# New_Grads_2019_Keychain.net
KiCad netlist of a schematic drawn in EAGLE
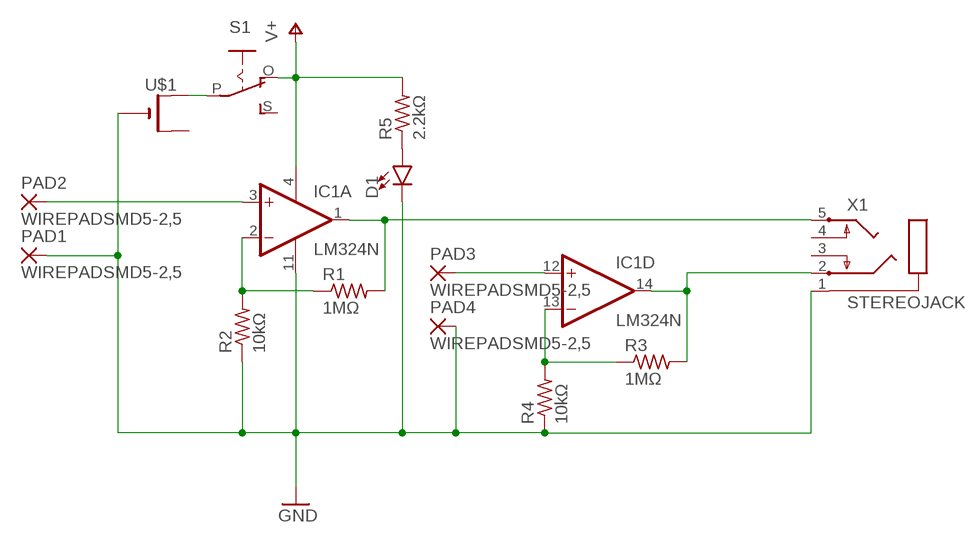
[diagram p0: schematic, sheet 1]

(export (version "E")
  (design (tool "Eeschema 10.0.6"))
  (components
    (comp (ref "D1")
      (value "LED-3MM-NO_SILK")
      (footprint "eagle-import:LED_3MM-NS")
      (libsource (lib "eagle-import") (part "LED-3MM-NO_SILK"))
    )
    (comp (ref "IC1")
      (value "LM324N")
      (footprint "eagle-import:DIL14")
      (libsource (lib "eagle-import") (part "LM324N"))
    )
    (comp (ref "PAD1")
      (value "WIREPADSMD5-2,5")
      (footprint "eagle-import:5-2,5")
      (libsource (lib "eagle-import") (part "WIREPADSMD5-2,5"))
    )
    (comp (ref "PAD2")
      (value "WIREPADSMD5-2,5")
      (footprint "eagle-import:5-2,5")
      (libsource (lib "eagle-import") (part "WIREPADSMD5-2,5"))
    )
    (comp (ref "PAD3")
      (value "WIREPADSMD5-2,5")
      (footprint "eagle-import:5-2,5")
      (libsource (lib "eagle-import") (part "WIREPADSMD5-2,5"))
    )
    (comp (ref "PAD4")
      (value "WIREPADSMD5-2,5")
      (footprint "eagle-import:5-2,5")
      (libsource (lib "eagle-import") (part "WIREPADSMD5-2,5"))
    )
    (comp (ref "R1")
      (value "1MΩ")
      (footprint "eagle-import:0204_5")
      (libsource (lib "eagle-import") (part "R-US_0204/5"))
    )
    (comp (ref "R2")
      (value "10kΩ")
      (footprint "eagle-import:0204_5")
      (libsource (lib "eagle-import") (part "R-US_0204/5"))
    )
    (comp (ref "R3")
      (value "1MΩ")
      (footprint "eagle-import:0204_5")
      (libsource (lib "eagle-import") (part "R-US_0204/5"))
    )
    (comp (ref "R4")
      (value "10kΩ")
      (footprint "eagle-import:0204_5")
      (libsource (lib "eagle-import") (part "R-US_0204/5"))
    )
    (comp (ref "R5")
      (value "2.2kΩ")
      (footprint "eagle-import:0204_5")
      (libsource (lib "eagle-import") (part "R-US_0204/5"))
    )
    (comp (ref "S1")
      (value "EG1218S")
      (footprint "eagle-import:EG1218")
      (libsource (lib "eagle-import") (part "EG1218S"))
    )
    (comp (ref "U$1")
      (value "CR1220THM")
      (footprint "eagle-import:CR1220-THM")
      (libsource (lib "eagle-import") (part "CR1220THM"))
    )
    (comp (ref "X1")
      (value "STEREOJACK")
      (footprint "eagle-import:STX3100")
      (libsource (lib "eagle-import") (part "STEREOJACK"))
    )
  )
  (nets
    (net (code "1") (name "GND") (class "Default")
      (node (ref "D1") (pin "K") (pinfunction "C_K") (pintype "passive"))
      (node (ref "IC1") (pin "11") (pinfunction "V-_11") (pintype "power_in"))
      (node (ref "PAD1") (pin "1") (pinfunction "P_1") (pintype "passive"))
      (node (ref "PAD4") (pin "1") (pinfunction "P_1") (pintype "passive"))
      (node (ref "R2") (pin "1") (pinfunction "1_1") (pintype "passive"))
      (node (ref "R4") (pin "1") (pinfunction "1_1") (pintype "passive"))
      (node (ref "U$1") (pin "-") (pinfunction "-_-") (pintype "passive"))
      (node (ref "X1") (pin "1") (pinfunction "1_1") (pintype "passive"))
    )
    (net (code "2") (name "Net-(D1-PadA)") (class "Default")
      (node (ref "D1") (pin "A") (pinfunction "A_A") (pintype "passive"))
      (node (ref "R5") (pin "1") (pinfunction "1_1") (pintype "passive"))
    )
    (net (code "3") (name "Net-(IC1A-+IN)") (class "Default")
      (node (ref "IC1") (pin "3") (pinfunction "+IN_3") (pintype "input"))
      (node (ref "PAD2") (pin "1") (pinfunction "P_1") (pintype "passive"))
    )
    (net (code "4") (name "Net-(IC1A--IN)") (class "Default")
      (node (ref "IC1") (pin "2") (pinfunction "-IN_2") (pintype "input"))
      (node (ref "R1") (pin "1") (pinfunction "1_1") (pintype "passive"))
      (node (ref "R2") (pin "2") (pinfunction "2_2") (pintype "passive"))
    )
    (net (code "5") (name "Net-(IC1A-OUT)") (class "Default")
      (node (ref "IC1") (pin "1") (pinfunction "OUT_1") (pintype "output"))
      (node (ref "R1") (pin "2") (pinfunction "2_2") (pintype "passive"))
      (node (ref "X1") (pin "5") (pinfunction "5_5") (pintype "passive"))
    )
    (net (code "6") (name "Net-(IC1D-+IN)") (class "Default")
      (node (ref "IC1") (pin "12") (pinfunction "+IN_12") (pintype "input"))
      (node (ref "PAD3") (pin "1") (pinfunction "P_1") (pintype "passive"))
    )
    (net (code "7") (name "Net-(IC1D--IN)") (class "Default")
      (node (ref "IC1") (pin "13") (pinfunction "-IN_13") (pintype "input"))
      (node (ref "R3") (pin "1") (pinfunction "1_1") (pintype "passive"))
      (node (ref "R4") (pin "2") (pinfunction "2_2") (pintype "passive"))
    )
    (net (code "8") (name "Net-(IC1D-OUT)") (class "Default")
      (node (ref "IC1") (pin "14") (pinfunction "OUT_14") (pintype "output"))
      (node (ref "R3") (pin "2") (pinfunction "2_2") (pintype "passive"))
      (node (ref "X1") (pin "2") (pinfunction "2_2") (pintype "passive"))
    )
    (net (code "9") (name "Net-(U$1-+)") (class "Default")
      (node (ref "S1") (pin "P") (pinfunction "P_P") (pintype "passive"))
      (node (ref "U$1") (pin "+1") (pinfunction "+_+1") (pintype "passive"))
    )
    (net (code "10") (name "V+") (class "Default")
      (node (ref "IC1") (pin "4") (pinfunction "V+_4") (pintype "power_in"))
      (node (ref "R5") (pin "2") (pinfunction "2_2") (pintype "passive"))
      (node (ref "S1") (pin "O") (pinfunction "O_O") (pintype "passive"))
    )
    (net (code "11") (name "unconnected-(S1-PadS)") (class "Default")
      (node (ref "S1") (pin "S") (pinfunction "S_S") (pintype "passive"))
    )
    (net (code "12") (name "unconnected-(U$1-+1-Pad+2)") (class "Default")
      (node (ref "U$1") (pin "+2") (pinfunction "+1_+2") (pintype "passive"))
    )
    (net (code "13") (name "unconnected-(X1-Pad3)") (class "Default")
      (node (ref "X1") (pin "3") (pinfunction "3_3") (pintype "passive"))
    )
    (net (code "14") (name "unconnected-(X1-Pad4)") (class "Default")
      (node (ref "X1") (pin "4") (pinfunction "4_4") (pintype "passive"))
    )
  )
)
